# Sheet1.net
KiCad netlist of a schematic drawn in Altium Designer
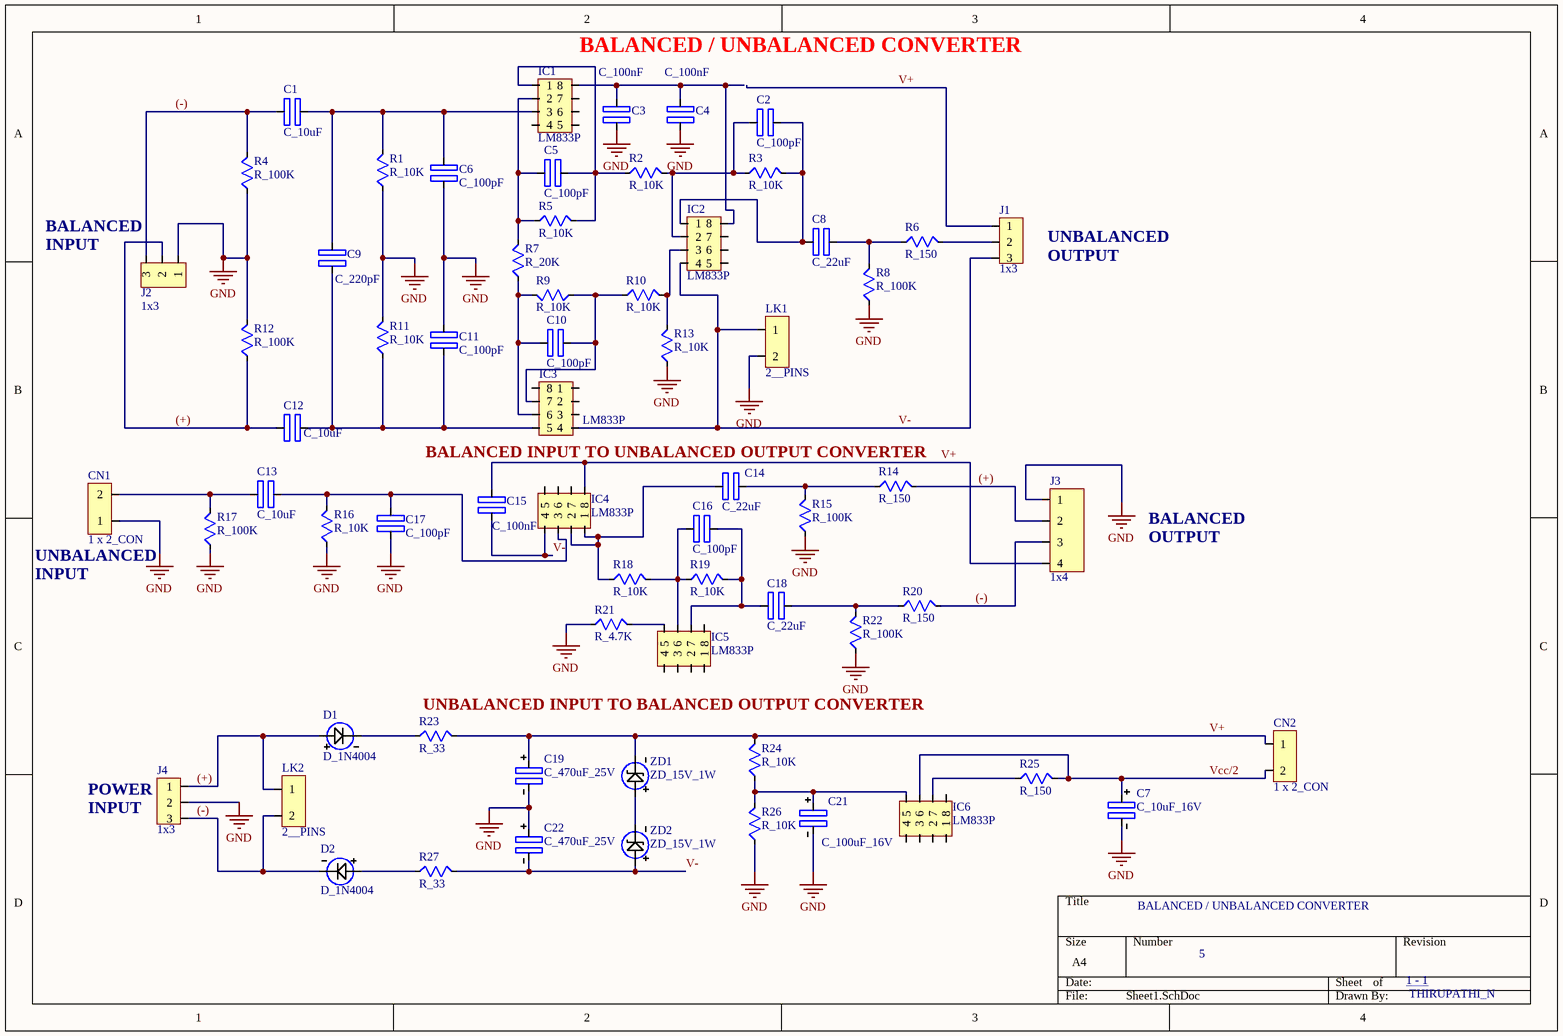
[diagram p0: Sheet1.SchDoc]

(export (version "E")
  (design (tool "Eeschema 10.0.6"))
  (components
    (comp (ref "C1")
      (value "C_10uF")
      (footprint "C_10uF")
      (description "CAP ALUM 10UF 20% 400V RADIAL")
      (fields
        (field (name "MANUFACTURER") "Nichicon")
        (field (name "MANUFACTURER PART NUMBER") "UCA2G100MPD1TD")
      )
      (libsource (lib "Schlib1") (part "C_10uF"))
    )
    (comp (ref "C2")
      (value "C_100pF")
      (footprint "C_100pF")
      (description "CAPACITOR CERAMIC 100PF 3000V C0G 5%, RAD")
      (fields
        (field (name "MANUFACTURER") "KEMET")
        (field (name "MANUFACTURER PART NUMBER") "C330C101JHG5TA")
      )
      (libsource (lib "Schlib1") (part "C_100pF"))
    )
    (comp (ref "C3")
      (value "C_100nF")
      (footprint "C_100nF")
      (description "NICHICON   UVR2A0R1MDD1TD   ALUMINUM ELECTROLYTIC CAPACITOR, 0.1UF, 100V, 20%, RADIAL")
      (fields
        (field (name "MANUFACTURER") "Nichicon")
        (field (name "MANUFACTURER PART NUMBER") "UVR2A0R1MDD1TD")
      )
      (libsource (lib "Schlib1") (part "C_100nF"))
    )
    (comp (ref "C4")
      (value "C_100nF")
      (footprint "C_100nF")
      (description "NICHICON   UVR2A0R1MDD1TD   ALUMINUM ELECTROLYTIC CAPACITOR, 0.1UF, 100V, 20%, RADIAL")
      (fields
        (field (name "MANUFACTURER") "Nichicon")
        (field (name "MANUFACTURER PART NUMBER") "UVR2A0R1MDD1TD")
      )
      (libsource (lib "Schlib1") (part "C_100nF"))
    )
    (comp (ref "C5")
      (value "C_100pF")
      (footprint "C_100pF")
      (description "CAPACITOR CERAMIC 100PF 3000V C0G 5%, RAD")
      (fields
        (field (name "MANUFACTURER") "KEMET")
        (field (name "MANUFACTURER PART NUMBER") "C330C101JHG5TA")
      )
      (libsource (lib "Schlib1") (part "C_100pF"))
    )
    (comp (ref "C6")
      (value "C_100pF")
      (footprint "C_100pF")
      (description "CAPACITOR CERAMIC 100PF 3000V C0G 5%, RAD")
      (fields
        (field (name "MANUFACTURER") "KEMET")
        (field (name "MANUFACTURER PART NUMBER") "C330C101JHG5TA")
      )
      (libsource (lib "Schlib1") (part "C_100pF"))
    )
    (comp (ref "C7")
      (value "C_10uF_16V")
      (footprint "C_10uF_16V")
      (description "CAPACITOR ALUM ELECT, 10UF, 16V, 20%, RADIAL")
      (fields
        (field (name "MANUFACTURER") "Nichicon")
        (field (name "MANUFACTURER PART NUMBER") "UST1C100MDD1TE")
      )
      (libsource (lib "Schlib1") (part "C_10uF_16V"))
    )
    (comp (ref "C8")
      (value "C_22uF")
      (footprint "C_22uF")
      (description "Cap Aluminum Lytic 22uF 50V 20% (5 X 11mm) Radial 2.5mm 95mA 2000h 85C Ammo Pack")
      (fields
        (field (name "MANUFACTURER") "Nichicon")
        (field (name "MANUFACTURER PART NUMBER") "UVR1H220MDD1TD")
      )
      (libsource (lib "Schlib1") (part "C_22uF"))
    )
    (comp (ref "C9")
      (value "C_220pF")
      (footprint "C_220pF")
      (fields
        (field (name "MANUFACTURER") "Vishay BCcomponents")
        (field (name "MANUFACTURER PART NUMBER") "F221K25Y5RN6UK5R")
        (field (name "TOLERANCE") "10%")
      )
      (libsource (lib "Schlib1") (part "C_220pF"))
    )
    (comp (ref "C10")
      (value "C_100pF")
      (footprint "C_100pF")
      (description "CAPACITOR CERAMIC 100PF 3000V C0G 5%, RAD")
      (fields
        (field (name "MANUFACTURER") "KEMET")
        (field (name "MANUFACTURER PART NUMBER") "C330C101JHG5TA")
      )
      (libsource (lib "Schlib1") (part "C_100pF"))
    )
    (comp (ref "C11")
      (value "C_100pF")
      (footprint "C_100pF")
      (description "CAPACITOR CERAMIC 100PF 3000V C0G 5%, RAD")
      (fields
        (field (name "MANUFACTURER") "KEMET")
        (field (name "MANUFACTURER PART NUMBER") "C330C101JHG5TA")
      )
      (libsource (lib "Schlib1") (part "C_100pF"))
    )
    (comp (ref "C12")
      (value "C_10uF")
      (footprint "C_10uF")
      (description "CAP ALUM 10UF 20% 400V RADIAL")
      (fields
        (field (name "MANUFACTURER") "Nichicon")
        (field (name "MANUFACTURER PART NUMBER") "UCA2G100MPD1TD")
      )
      (libsource (lib "Schlib1") (part "C_10uF"))
    )
    (comp (ref "C13")
      (value "C_10uF")
      (footprint "C_10uF")
      (description "CAP ALUM 10UF 20% 400V RADIAL")
      (fields
        (field (name "MANUFACTURER") "Nichicon")
        (field (name "MANUFACTURER PART NUMBER") "UCA2G100MPD1TD")
      )
      (libsource (lib "Schlib1") (part "C_10uF"))
    )
    (comp (ref "C14")
      (value "C_22uF")
      (footprint "C_22uF")
      (description "Cap Aluminum Lytic 22uF 50V 20% (5 X 11mm) Radial 2.5mm 95mA 2000h 85C Ammo Pack")
      (fields
        (field (name "MANUFACTURER") "Nichicon")
        (field (name "MANUFACTURER PART NUMBER") "UVR1H220MDD1TD")
      )
      (libsource (lib "Schlib1") (part "C_22uF"))
    )
    (comp (ref "C15")
      (value "C_100nF")
      (footprint "C_100nF")
      (description "NICHICON   UVR2A0R1MDD1TD   ALUMINUM ELECTROLYTIC CAPACITOR, 0.1UF, 100V, 20%, RADIAL")
      (fields
        (field (name "MANUFACTURER") "Nichicon")
        (field (name "MANUFACTURER PART NUMBER") "UVR2A0R1MDD1TD")
      )
      (libsource (lib "Schlib1") (part "C_100nF"))
    )
    (comp (ref "C16")
      (value "C_100pF")
      (footprint "C_100pF")
      (description "CAPACITOR CERAMIC 100PF 3000V C0G 5%, RAD")
      (fields
        (field (name "MANUFACTURER") "KEMET")
        (field (name "MANUFACTURER PART NUMBER") "C330C101JHG5TA")
      )
      (libsource (lib "Schlib1") (part "C_100pF"))
    )
    (comp (ref "C17")
      (value "C_100pF")
      (footprint "C_100pF")
      (description "CAPACITOR CERAMIC 100PF 3000V C0G 5%, RAD")
      (fields
        (field (name "MANUFACTURER") "KEMET")
        (field (name "MANUFACTURER PART NUMBER") "C330C101JHG5TA")
      )
      (libsource (lib "Schlib1") (part "C_100pF"))
    )
    (comp (ref "C18")
      (value "C_22uF")
      (footprint "C_22uF")
      (description "Cap Aluminum Lytic 22uF 50V 20% (5 X 11mm) Radial 2.5mm 95mA 2000h 85C Ammo Pack")
      (fields
        (field (name "MANUFACTURER") "Nichicon")
        (field (name "MANUFACTURER PART NUMBER") "UVR1H220MDD1TD")
      )
      (libsource (lib "Schlib1") (part "C_22uF"))
    )
    (comp (ref "C19")
      (value "C_470uF_25V")
      (footprint "C_25V_470uF")
      (fields
        (field (name "MANUFACTURER") "Nichicon")
        (field (name "MANUFACTURER PART NUMBER") "UHE1E471MPD6TD")
        (field (name "TOLERANCE") "20%")
      )
      (libsource (lib "Schlib1") (part "C_470uF_25V"))
    )
    (comp (ref "C21")
      (value "C_100uF_16V")
      (footprint "C_100uF_16V")
      (description "Cap Aluminum Lytic 100uF 16V 20% (6.3 X 7mm) Radial 2.5mm 110mA 1000h 105°C Ammo")
      (fields
        (field (name "MANUFACTURER") "KEMET")
        (field (name "MANUFACTURER PART NUMBER") "ESS107M016AE2EA")
      )
      (libsource (lib "Schlib1") (part "C_100uF_16V"))
    )
    (comp (ref "C22")
      (value "C_470uF_25V")
      (footprint "C_25V_470uF")
      (fields
        (field (name "MANUFACTURER") "Nichicon")
        (field (name "MANUFACTURER PART NUMBER") "UHE1E471MPD6TD")
        (field (name "TOLERANCE") "20%")
      )
      (libsource (lib "Schlib1") (part "C_470uF_25V"))
    )
    (comp (ref "CN1")
      (value "1 x 2_CON")
      (footprint "1*2_CONNECTOR")
      (description "TERM BLK 2POS SIDE ENTRY 5MM PCB")
      (fields
        (field (name "MANUFACTURER") "Wurth Electronics")
        (field (name "MANUFACTURER PART NUMBER") "691137710002")
      )
      (libsource (lib "") (part "1 x 2_CON_1"))
    )
    (comp (ref "CN2")
      (value "1 x 2_CON")
      (footprint "1*2_CONNECTOR")
      (description "TERM BLK 2POS SIDE ENTRY 5MM PCB")
      (fields
        (field (name "MANUFACTURER") "Wurth Electronics")
        (field (name "MANUFACTURER PART NUMBER") "691137710002")
      )
      (libsource (lib "Schlib1") (part "1 x 2_CON"))
    )
    (comp (ref "D1")
      (value "D_1N4004")
      (footprint "D_IN4004")
      (description "DIODES INC. - 1N4004-T - Standard Recovery Diode, 400 V, 1 A, Single, 1 V, 30 A")
      (fields (field (name "MANUFACTURER") "Diodes") (field (name "MANUFACTURER PART NUMBER") "1N4004-T"))
      (libsource (lib "Schlib1") (part "D_1N4004"))
    )
    (comp (ref "D2")
      (value "D_1N4004")
      (footprint "D_IN4004")
      (description "DIODES INC. - 1N4004-T - Standard Recovery Diode, 400 V, 1 A, Single, 1 V, 30 A")
      (fields (field (name "MANUFACTURER") "Diodes") (field (name "MANUFACTURER PART NUMBER") "1N4004-T"))
      (libsource (lib "Schlib1") (part "D_1N4004"))
    )
    (comp (ref "IC1")
      (value "LM833P")
      (footprint "IC_833")
      (description "OP Amp Dual GP 18V/36V 8-Pin PDIP Tube")
      (fields (field (name "MANUFACTURER") "Texas Instruments"))
      (libsource (lib "Schlib1") (part "LM833P"))
    )
    (comp (ref "IC2")
      (value "LM833P")
      (footprint "IC_833")
      (description "OP Amp Dual GP 18V/36V 8-Pin PDIP Tube")
      (fields (field (name "MANUFACTURER") "Texas Instruments"))
      (libsource (lib "Schlib1") (part "LM833P"))
    )
    (comp (ref "IC3")
      (value "LM833P")
      (footprint "IC_833")
      (description "OP Amp Dual GP 18V/36V 8-Pin PDIP Tube")
      (fields (field (name "MANUFACTURER") "Texas Instruments"))
      (libsource (lib "") (part "LM833P_1"))
    )
    (comp (ref "IC4")
      (value "LM833P")
      (footprint "IC_833")
      (description "OP Amp Dual GP 18V/36V 8-Pin PDIP Tube")
      (fields (field (name "MANUFACTURER") "Texas Instruments"))
      (libsource (lib "Schlib1") (part "LM833P"))
    )
    (comp (ref "IC5")
      (value "LM833P")
      (footprint "IC_833")
      (description "OP Amp Dual GP 18V/36V 8-Pin PDIP Tube")
      (fields (field (name "MANUFACTURER") "Texas Instruments"))
      (libsource (lib "Schlib1") (part "LM833P"))
    )
    (comp (ref "IC6")
      (value "LM833P")
      (footprint "IC_833")
      (description "OP Amp Dual GP 18V/36V 8-Pin PDIP Tube")
      (fields (field (name "MANUFACTURER") "Texas Instruments"))
      (libsource (lib "Schlib1") (part "LM833P"))
    )
    (comp (ref "J1")
      (value "1x3")
      (footprint "1*3_CONNECTOR")
      (description "Fixed Terminal Blocks WR-TBL SMT Model7097 3Pin 5mm Hztl")
      (fields
        (field (name "MANUFACTURER") "Wurth Electronics Midcom")
        (field (name "MANUFACTURER PART NUMBER") "691709710303")
      )
      (libsource (lib "") (part "1x3_1"))
    )
    (comp (ref "J2")
      (value "1x3")
      (footprint "1*3_CONNECTOR")
      (description "Fixed Terminal Blocks WR-TBL SMT Model7097 3Pin 5mm Hztl")
      (fields
        (field (name "MANUFACTURER") "Wurth Electronics Midcom")
        (field (name "MANUFACTURER PART NUMBER") "691709710303")
      )
      (libsource (lib "Schlib1") (part "1x3"))
    )
    (comp (ref "J3")
      (value "1x4")
      (footprint "1*4_CONNECTOR")
      (description "TERM BLK 4POS SIDE ENTRY 5MM PCB")
      (fields
        (field (name "MANUFACTURER") "Wurth Electronics")
        (field (name "MANUFACTURER PART NUMBER") "691137710004")
      )
      (libsource (lib "Schlib1") (part "1x4"))
    )
    (comp (ref "J4")
      (value "1x3")
      (footprint "1*3_CONNECTOR")
      (description "Fixed Terminal Blocks WR-TBL SMT Model7097 3Pin 5mm Hztl")
      (fields
        (field (name "MANUFACTURER") "Wurth Electronics Midcom")
        (field (name "MANUFACTURER PART NUMBER") "691709710303")
      )
      (libsource (lib "Schlib1") (part "1x3"))
    )
    (comp (ref "LK1")
      (value "2__PINS")
      (footprint "2_PIN")
      (description "HARWIN - M20-9990246 - CONNECTOR, HEADER, 2 POSITION, 1ROW, 2.54MM")
      (fields (field (name "MANUFACTURER") "Harwin") (field (name "MANUFACTURER PART NUMBER") "M20-9990246"))
      (libsource (lib "Schlib1") (part "2__PINS"))
    )
    (comp (ref "LK2")
      (value "2__PINS")
      (footprint "2_PIN")
      (description "HARWIN - M20-9990246 - CONNECTOR, HEADER, 2 POSITION, 1ROW, 2.54MM")
      (fields (field (name "MANUFACTURER") "Harwin") (field (name "MANUFACTURER PART NUMBER") "M20-9990246"))
      (libsource (lib "Schlib1") (part "2__PINS"))
    )
    (comp (ref "R1")
      (value "R_10K")
      (footprint "CF_RESISTOR_FP")
      (description "RES 10K OHM 1/4W 5% AXIAL")
      (fields
        (field (name "MANUFACTURER") "Stackpole Electronics")
        (field (name "MANUFACTURER PART NUMBER") "CF14JT10K0")
      )
      (libsource (lib "Schlib1") (part "R_10K"))
    )
    (comp (ref "R2")
      (value "R_10K")
      (footprint "CF_RESISTOR_FP")
      (description "RES 10K OHM 1/4W 5% AXIAL")
      (fields
        (field (name "MANUFACTURER") "Stackpole Electronics")
        (field (name "MANUFACTURER PART NUMBER") "CF14JT10K0")
      )
      (libsource (lib "Schlib1") (part "R_10K"))
    )
    (comp (ref "R3")
      (value "R_10K")
      (footprint "CF_RESISTOR_FP")
      (description "RES 10K OHM 1/4W 5% AXIAL")
      (fields
        (field (name "MANUFACTURER") "Stackpole Electronics")
        (field (name "MANUFACTURER PART NUMBER") "CF14JT10K0")
      )
      (libsource (lib "Schlib1") (part "R_10K"))
    )
    (comp (ref "R4")
      (value "R_100K")
      (footprint "CF_RESISTOR_FP")
      (description "RES 100K OHM 1/4W 5% AXIAL")
      (fields
        (field (name "MANUFACTURER") "Stackpole Electronics")
        (field (name "MANUFACTURER PART NUMBER") "CF14JT100K")
      )
      (libsource (lib "Schlib1") (part "R_100K"))
    )
    (comp (ref "R5")
      (value "R_10K")
      (footprint "CF_RESISTOR_FP")
      (description "RES 10K OHM 1/4W 5% AXIAL")
      (fields
        (field (name "MANUFACTURER") "Stackpole Electronics")
        (field (name "MANUFACTURER PART NUMBER") "CF14JT10K0")
      )
      (libsource (lib "Schlib1") (part "R_10K"))
    )
    (comp (ref "R6")
      (value "R_150")
      (footprint "CF_RESISTOR_FP")
      (description "Res Carbon Film 150 Ohm 5% 1/4W -400ppm/C to 0ppm/C Conformal AXL Thru-Hole T/R")
      (fields
        (field (name "MANUFACTURER") "Stackpole Electronics")
        (field (name "MANUFACTURER PART NUMBER") "CF14JT150R")
      )
      (libsource (lib "Schlib1") (part "R_150"))
    )
    (comp (ref "R7")
      (value "R_20K")
      (footprint "CF_RESISTOR_FP")
      (description "RES 20K OHM 1/2W 5% AXIAL")
      (fields
        (field (name "MANUFACTURER") "Stackpole Electronics")
        (field (name "MANUFACTURER PART NUMBER") "CF12JT20K0")
      )
      (libsource (lib "Schlib1") (part "R_20K"))
    )
    (comp (ref "R8")
      (value "R_100K")
      (footprint "CF_RESISTOR_FP")
      (description "RES 100K OHM 1/4W 5% AXIAL")
      (fields
        (field (name "MANUFACTURER") "Stackpole Electronics")
        (field (name "MANUFACTURER PART NUMBER") "CF14JT100K")
      )
      (libsource (lib "Schlib1") (part "R_100K"))
    )
    (comp (ref "R9")
      (value "R_10K")
      (footprint "CF_RESISTOR_FP")
      (description "RES 10K OHM 1/4W 5% AXIAL")
      (fields
        (field (name "MANUFACTURER") "Stackpole Electronics")
        (field (name "MANUFACTURER PART NUMBER") "CF14JT10K0")
      )
      (libsource (lib "Schlib1") (part "R_10K"))
    )
    (comp (ref "R10")
      (value "R_10K")
      (footprint "CF_RESISTOR_FP")
      (description "RES 10K OHM 1/4W 5% AXIAL")
      (fields
        (field (name "MANUFACTURER") "Stackpole Electronics")
        (field (name "MANUFACTURER PART NUMBER") "CF14JT10K0")
      )
      (libsource (lib "Schlib1") (part "R_10K"))
    )
    (comp (ref "R11")
      (value "R_10K")
      (footprint "CF_RESISTOR_FP")
      (description "RES 10K OHM 1/4W 5% AXIAL")
      (fields
        (field (name "MANUFACTURER") "Stackpole Electronics")
        (field (name "MANUFACTURER PART NUMBER") "CF14JT10K0")
      )
      (libsource (lib "Schlib1") (part "R_10K"))
    )
    (comp (ref "R12")
      (value "R_100K")
      (footprint "CF_RESISTOR_FP")
      (description "RES 100K OHM 1/4W 5% AXIAL")
      (fields
        (field (name "MANUFACTURER") "Stackpole Electronics")
        (field (name "MANUFACTURER PART NUMBER") "CF14JT100K")
      )
      (libsource (lib "Schlib1") (part "R_100K"))
    )
    (comp (ref "R13")
      (value "R_10K")
      (footprint "CF_RESISTOR_FP")
      (description "RES 10K OHM 1/4W 5% AXIAL")
      (fields
        (field (name "MANUFACTURER") "Stackpole Electronics")
        (field (name "MANUFACTURER PART NUMBER") "CF14JT10K0")
      )
      (libsource (lib "Schlib1") (part "R_10K"))
    )
    (comp (ref "R14")
      (value "R_150")
      (footprint "CF_RESISTOR_FP")
      (description "Res Carbon Film 150 Ohm 5% 1/4W -400ppm/C to 0ppm/C Conformal AXL Thru-Hole T/R")
      (fields
        (field (name "MANUFACTURER") "Stackpole Electronics")
        (field (name "MANUFACTURER PART NUMBER") "CF14JT150R")
      )
      (libsource (lib "Schlib1") (part "R_150"))
    )
    (comp (ref "R15")
      (value "R_100K")
      (footprint "CF_RESISTOR_FP")
      (description "RES 100K OHM 1/4W 5% AXIAL")
      (fields
        (field (name "MANUFACTURER") "Stackpole Electronics")
        (field (name "MANUFACTURER PART NUMBER") "CF14JT100K")
      )
      (libsource (lib "Schlib1") (part "R_100K"))
    )
    (comp (ref "R16")
      (value "R_10K")
      (footprint "CF_RESISTOR_FP")
      (description "RES 10K OHM 1/4W 5% AXIAL")
      (fields
        (field (name "MANUFACTURER") "Stackpole Electronics")
        (field (name "MANUFACTURER PART NUMBER") "CF14JT10K0")
      )
      (libsource (lib "Schlib1") (part "R_10K"))
    )
    (comp (ref "R17")
      (value "R_100K")
      (footprint "CF_RESISTOR_FP")
      (description "RES 100K OHM 1/4W 5% AXIAL")
      (fields
        (field (name "MANUFACTURER") "Stackpole Electronics")
        (field (name "MANUFACTURER PART NUMBER") "CF14JT100K")
      )
      (libsource (lib "Schlib1") (part "R_100K"))
    )
    (comp (ref "R18")
      (value "R_10K")
      (footprint "CF_RESISTOR_FP")
      (description "RES 10K OHM 1/4W 5% AXIAL")
      (fields
        (field (name "MANUFACTURER") "Stackpole Electronics")
        (field (name "MANUFACTURER PART NUMBER") "CF14JT10K0")
      )
      (libsource (lib "Schlib1") (part "R_10K"))
    )
    (comp (ref "R19")
      (value "R_10K")
      (footprint "CF_RESISTOR_FP")
      (description "RES 10K OHM 1/4W 5% AXIAL")
      (fields
        (field (name "MANUFACTURER") "Stackpole Electronics")
        (field (name "MANUFACTURER PART NUMBER") "CF14JT10K0")
      )
      (libsource (lib "Schlib1") (part "R_10K"))
    )
    (comp (ref "R20")
      (value "R_150")
      (footprint "CF_RESISTOR_FP")
      (description "Res Carbon Film 150 Ohm 5% 1/4W -400ppm/C to 0ppm/C Conformal AXL Thru-Hole T/R")
      (fields
        (field (name "MANUFACTURER") "Stackpole Electronics")
        (field (name "MANUFACTURER PART NUMBER") "CF14JT150R")
      )
      (libsource (lib "Schlib1") (part "R_150"))
    )
    (comp (ref "R21")
      (value "R_4.7K")
      (footprint "R_4.7K")
      (fields
        (field (name "MANUFACTURER") "Ohmite")
        (field (name "MANUFACTURER PART NUMBER") "OY472KE")
        (field (name "TOLERANCE") "10%")
      )
      (libsource (lib "Schlib1") (part "R_4.7K"))
    )
    (comp (ref "R22")
      (value "R_100K")
      (footprint "CF_RESISTOR_FP")
      (description "RES 100K OHM 1/4W 5% AXIAL")
      (fields
        (field (name "MANUFACTURER") "Stackpole Electronics")
        (field (name "MANUFACTURER PART NUMBER") "CF14JT100K")
      )
      (libsource (lib "Schlib1") (part "R_100K"))
    )
    (comp (ref "R23")
      (value "R_33")
      (footprint "CF_RESISTOR_FP")
      (description "RES 33 OHM 1/2W 5% AXIAL")
      (fields
        (field (name "MANUFACTURER") "Stackpole Electronics")
        (field (name "MANUFACTURER PART NUMBER") "CF12JT33R0")
      )
      (libsource (lib "Schlib1") (part "R_33"))
    )
    (comp (ref "R24")
      (value "R_10K")
      (footprint "CF_RESISTOR_FP")
      (description "RES 10K OHM 1/4W 5% AXIAL")
      (fields
        (field (name "MANUFACTURER") "Stackpole Electronics")
        (field (name "MANUFACTURER PART NUMBER") "CF14JT10K0")
      )
      (libsource (lib "Schlib1") (part "R_10K"))
    )
    (comp (ref "R25")
      (value "R_150")
      (footprint "CF_RESISTOR_FP")
      (description "Res Carbon Film 150 Ohm 5% 1/4W -400ppm/C to 0ppm/C Conformal AXL Thru-Hole T/R")
      (fields
        (field (name "MANUFACTURER") "Stackpole Electronics")
        (field (name "MANUFACTURER PART NUMBER") "CF14JT150R")
      )
      (libsource (lib "Schlib1") (part "R_150"))
    )
    (comp (ref "R26")
      (value "R_10K")
      (footprint "CF_RESISTOR_FP")
      (description "RES 10K OHM 1/4W 5% AXIAL")
      (fields
        (field (name "MANUFACTURER") "Stackpole Electronics")
        (field (name "MANUFACTURER PART NUMBER") "CF14JT10K0")
      )
      (libsource (lib "Schlib1") (part "R_10K"))
    )
    (comp (ref "R27")
      (value "R_33")
      (footprint "CF_RESISTOR_FP")
      (description "RES 33 OHM 1/2W 5% AXIAL")
      (fields
        (field (name "MANUFACTURER") "Stackpole Electronics")
        (field (name "MANUFACTURER PART NUMBER") "CF12JT33R0")
      )
      (libsource (lib "Schlib1") (part "R_33"))
    )
    (comp (ref "ZD1")
      (value "ZD_15V_1W")
      (footprint "ZR_15V_1W")
      (description "GLOVE, POLYAMIDE, L/FREE, PU, SIZE 6 - More Details")
      (fields
        (field (name "MANUFACTURER") "NXP Semiconductors")
        (field (name "MANUFACTURER PART NUMBER") "BZV85-C15,113")
      )
      (libsource (lib "Schlib1") (part "ZD_15V_1W"))
    )
    (comp (ref "ZD2")
      (value "ZD_15V_1W")
      (footprint "ZR_15V_1W")
      (description "GLOVE, POLYAMIDE, L/FREE, PU, SIZE 6 - More Details")
      (fields
        (field (name "MANUFACTURER") "NXP Semiconductors")
        (field (name "MANUFACTURER PART NUMBER") "BZV85-C15,113")
      )
      (libsource (lib "Schlib1") (part "ZD_15V_1W"))
    )
  )
  (nets
    (net (code "1") (name "/(+)") (class "Default")
      (node (ref "C12") (pin "0") (pinfunction "0_0") (pintype "passive"))
      (node (ref "D1") (pin "2") (pinfunction "2_2") (pintype "passive"))
      (node (ref "J2") (pin "2") (pinfunction "2_2") (pintype "passive"))
      (node (ref "J3") (pin "2") (pinfunction "2_2") (pintype "passive"))
      (node (ref "J4") (pin "1") (pinfunction "1_1") (pintype "passive"))
      (node (ref "LK2") (pin "1") (pinfunction "1_1") (pintype "passive"))
      (node (ref "R12") (pin "0") (pinfunction "0_0") (pintype "passive"))
      (node (ref "R14") (pin "1") (pinfunction "1_1") (pintype "passive"))
    )
    (net (code "2") (name "/(-)") (class "Default")
      (node (ref "C1") (pin "0") (pinfunction "0_0") (pintype "passive"))
      (node (ref "D2") (pin "1") (pinfunction "1_1") (pintype "passive"))
      (node (ref "J2") (pin "3") (pinfunction "3_3") (pintype "passive"))
      (node (ref "J3") (pin "3") (pinfunction "3_3") (pintype "passive"))
      (node (ref "J4") (pin "3") (pinfunction "3_3") (pintype "passive"))
      (node (ref "LK2") (pin "2") (pinfunction "2_2") (pintype "passive"))
      (node (ref "R20") (pin "1") (pinfunction "1_1") (pintype "passive"))
      (node (ref "R4") (pin "1") (pinfunction "1_1") (pintype "passive"))
    )
    (net (code "3") (name "/V+") (class "Default")
      (node (ref "C15") (pin "1") (pinfunction "1_1") (pintype "passive"))
      (node (ref "C19") (pin "0") (pinfunction "0_0") (pintype "passive"))
      (node (ref "CN2") (pin "1") (pinfunction "1_1") (pintype "passive"))
      (node (ref "IC4") (pin "8") (pinfunction "8_8") (pintype "passive"))
      (node (ref "J1") (pin "1") (pinfunction "1_1") (pintype "passive"))
      (node (ref "J3") (pin "4") (pinfunction "4_4") (pintype "passive"))
      (node (ref "R23") (pin "1") (pinfunction "1_1") (pintype "passive"))
      (node (ref "R24") (pin "1") (pinfunction "1_1") (pintype "passive"))
      (node (ref "ZD1") (pin "1") (pinfunction "1_1") (pintype "passive"))
    )
    (net (code "4") (name "/V-") (class "Default")
      (node (ref "C15") (pin "0") (pinfunction "0_0") (pintype "passive"))
      (node (ref "C22") (pin "1") (pinfunction "1_1") (pintype "passive"))
      (node (ref "IC2") (pin "4") (pinfunction "4_4") (pintype "passive"))
      (node (ref "IC3") (pin "4") (pinfunction "4_4") (pintype "passive"))
      (node (ref "IC4") (pin "4") (pinfunction "4_4") (pintype "passive"))
      (node (ref "J1") (pin "3") (pinfunction "3_3") (pintype "passive"))
      (node (ref "LK1") (pin "1") (pinfunction "1_1") (pintype "passive"))
      (node (ref "R27") (pin "1") (pinfunction "1_1") (pintype "passive"))
      (node (ref "ZD2") (pin "2") (pinfunction "2_2") (pintype "passive"))
    )
    (net (code "5") (name "/Vcc{slash}2") (class "Default")
      (node (ref "C7") (pin "0") (pinfunction "0_0") (pintype "passive"))
      (node (ref "CN2") (pin "2") (pinfunction "2_2") (pintype "passive"))
      (node (ref "IC6") (pin "6") (pinfunction "6_6") (pintype "passive"))
      (node (ref "R25") (pin "1") (pinfunction "1_1") (pintype "passive"))
    )
    (net (code "6") (name "GND") (class "Default")
      (node (ref "C11") (pin "1") (pinfunction "1_1") (pintype "passive"))
      (node (ref "C17") (pin "0") (pinfunction "0_0") (pintype "passive"))
      (node (ref "C19") (pin "1") (pinfunction "1_1") (pintype "passive"))
      (node (ref "C21") (pin "1") (pinfunction "1_1") (pintype "passive"))
      (node (ref "C22") (pin "0") (pinfunction "0_0") (pintype "passive"))
      (node (ref "C3") (pin "0") (pinfunction "0_0") (pintype "passive"))
      (node (ref "C4") (pin "0") (pinfunction "0_0") (pintype "passive"))
      (node (ref "C6") (pin "0") (pinfunction "0_0") (pintype "passive"))
      (node (ref "C7") (pin "1") (pinfunction "1_1") (pintype "passive"))
      (node (ref "CN1") (pin "1") (pinfunction "1_1") (pintype "passive"))
      (node (ref "J2") (pin "1") (pinfunction "1_1") (pintype "passive"))
      (node (ref "J3") (pin "1") (pinfunction "1_1") (pintype "passive"))
      (node (ref "J4") (pin "2") (pinfunction "2_2") (pintype "passive"))
      (node (ref "LK1") (pin "2") (pinfunction "2_2") (pintype "passive"))
      (node (ref "R1") (pin "0") (pinfunction "0_0") (pintype "passive"))
      (node (ref "R11") (pin "1") (pinfunction "1_1") (pintype "passive"))
      (node (ref "R12") (pin "1") (pinfunction "1_1") (pintype "passive"))
      (node (ref "R13") (pin "0") (pinfunction "0_0") (pintype "passive"))
      (node (ref "R15") (pin "0") (pinfunction "0_0") (pintype "passive"))
      (node (ref "R16") (pin "0") (pinfunction "0_0") (pintype "passive"))
      (node (ref "R17") (pin "0") (pinfunction "0_0") (pintype "passive"))
      (node (ref "R21") (pin "0") (pinfunction "0_0") (pintype "passive"))
      (node (ref "R22") (pin "0") (pinfunction "0_0") (pintype "passive"))
      (node (ref "R26") (pin "0") (pinfunction "0_0") (pintype "passive"))
      (node (ref "R4") (pin "0") (pinfunction "0_0") (pintype "passive"))
      (node (ref "R8") (pin "0") (pinfunction "0_0") (pintype "passive"))
    )
    (net (code "7") (name "Net-(C1-Pad1)") (class "Default")
      (node (ref "C1") (pin "1") (pinfunction "1_1") (pintype "passive"))
      (node (ref "C6") (pin "1") (pinfunction "1_1") (pintype "passive"))
      (node (ref "C9") (pin "1") (pinfunction "1_1") (pintype "passive"))
      (node (ref "IC1") (pin "3") (pinfunction "3_3") (pintype "passive"))
      (node (ref "R1") (pin "1") (pinfunction "1_1") (pintype "passive"))
    )
    (net (code "8") (name "Net-(C2-Pad0)") (class "Default")
      (node (ref "C2") (pin "0") (pinfunction "0_0") (pintype "passive"))
      (node (ref "IC2") (pin "2") (pinfunction "2_2") (pintype "passive"))
      (node (ref "R2") (pin "1") (pinfunction "1_1") (pintype "passive"))
      (node (ref "R3") (pin "0") (pinfunction "0_0") (pintype "passive"))
    )
    (net (code "9") (name "Net-(C2-Pad1)") (class "Default")
      (node (ref "C2") (pin "1") (pinfunction "1_1") (pintype "passive"))
      (node (ref "C8") (pin "0") (pinfunction "0_0") (pintype "passive"))
      (node (ref "IC2") (pin "1") (pinfunction "1_1") (pintype "passive"))
      (node (ref "R3") (pin "1") (pinfunction "1_1") (pintype "passive"))
    )
    (net (code "10") (name "Net-(C3-Pad1)") (class "Default")
      (node (ref "C3") (pin "1") (pinfunction "1_1") (pintype "passive"))
      (node (ref "C4") (pin "1") (pinfunction "1_1") (pintype "passive"))
      (node (ref "IC1") (pin "8") (pinfunction "8_8") (pintype "passive"))
      (node (ref "IC2") (pin "8") (pinfunction "8_8") (pintype "passive"))
    )
    (net (code "11") (name "Net-(C5-Pad0)") (class "Default")
      (node (ref "C5") (pin "0") (pinfunction "0_0") (pintype "passive"))
      (node (ref "IC1") (pin "2") (pinfunction "2_2") (pintype "passive"))
      (node (ref "R5") (pin "0") (pinfunction "0_0") (pintype "passive"))
      (node (ref "R7") (pin "1") (pinfunction "1_1") (pintype "passive"))
    )
    (net (code "12") (name "Net-(C5-Pad1)") (class "Default")
      (node (ref "C5") (pin "1") (pinfunction "1_1") (pintype "passive"))
      (node (ref "IC1") (pin "1") (pinfunction "1_1") (pintype "passive"))
      (node (ref "R2") (pin "0") (pinfunction "0_0") (pintype "passive"))
      (node (ref "R5") (pin "1") (pinfunction "1_1") (pintype "passive"))
    )
    (net (code "13") (name "Net-(C8-Pad1)") (class "Default")
      (node (ref "C8") (pin "1") (pinfunction "1_1") (pintype "passive"))
      (node (ref "R6") (pin "0") (pinfunction "0_0") (pintype "passive"))
      (node (ref "R8") (pin "1") (pinfunction "1_1") (pintype "passive"))
    )
    (net (code "14") (name "Net-(C10-Pad0)") (class "Default")
      (node (ref "C10") (pin "0") (pinfunction "0_0") (pintype "passive"))
      (node (ref "IC3") (pin "7") (pinfunction "7_7") (pintype "passive"))
      (node (ref "R10") (pin "0") (pinfunction "0_0") (pintype "passive"))
      (node (ref "R9") (pin "0") (pinfunction "0_0") (pintype "passive"))
    )
    (net (code "15") (name "Net-(C10-Pad1)") (class "Default")
      (node (ref "C10") (pin "1") (pinfunction "1_1") (pintype "passive"))
      (node (ref "IC3") (pin "6") (pinfunction "6_6") (pintype "passive"))
      (node (ref "R7") (pin "0") (pinfunction "0_0") (pintype "passive"))
      (node (ref "R9") (pin "1") (pinfunction "1_1") (pintype "passive"))
    )
    (net (code "16") (name "Net-(C11-Pad0)") (class "Default")
      (node (ref "C11") (pin "0") (pinfunction "0_0") (pintype "passive"))
      (node (ref "C12") (pin "1") (pinfunction "1_1") (pintype "passive"))
      (node (ref "C9") (pin "0") (pinfunction "0_0") (pintype "passive"))
      (node (ref "IC3") (pin "5") (pinfunction "5_5") (pintype "passive"))
      (node (ref "R11") (pin "0") (pinfunction "0_0") (pintype "passive"))
    )
    (net (code "17") (name "Net-(C13-Pad0)") (class "Default")
      (node (ref "C13") (pin "0") (pinfunction "0_0") (pintype "passive"))
      (node (ref "CN1") (pin "2") (pinfunction "2_2") (pintype "passive"))
      (node (ref "R17") (pin "1") (pinfunction "1_1") (pintype "passive"))
    )
    (net (code "18") (name "Net-(C13-Pad1)") (class "Default")
      (node (ref "C13") (pin "1") (pinfunction "1_1") (pintype "passive"))
      (node (ref "C17") (pin "1") (pinfunction "1_1") (pintype "passive"))
      (node (ref "IC4") (pin "3") (pinfunction "3_3") (pintype "passive"))
      (node (ref "R16") (pin "1") (pinfunction "1_1") (pintype "passive"))
    )
    (net (code "19") (name "Net-(C14-Pad0)") (class "Default")
      (node (ref "C14") (pin "0") (pinfunction "0_0") (pintype "passive"))
      (node (ref "IC4") (pin "1") (pinfunction "1_1") (pintype "passive"))
      (node (ref "IC4") (pin "2") (pinfunction "2_2") (pintype "passive"))
      (node (ref "R18") (pin "0") (pinfunction "0_0") (pintype "passive"))
    )
    (net (code "20") (name "Net-(C14-Pad1)") (class "Default")
      (node (ref "C14") (pin "1") (pinfunction "1_1") (pintype "passive"))
      (node (ref "R14") (pin "0") (pinfunction "0_0") (pintype "passive"))
      (node (ref "R15") (pin "1") (pinfunction "1_1") (pintype "passive"))
    )
    (net (code "21") (name "Net-(C16-Pad0)") (class "Default")
      (node (ref "C16") (pin "0") (pinfunction "0_0") (pintype "passive"))
      (node (ref "IC5") (pin "6") (pinfunction "6_6") (pintype "passive"))
      (node (ref "R18") (pin "1") (pinfunction "1_1") (pintype "passive"))
      (node (ref "R19") (pin "0") (pinfunction "0_0") (pintype "passive"))
    )
    (net (code "22") (name "Net-(C16-Pad1)") (class "Default")
      (node (ref "C16") (pin "1") (pinfunction "1_1") (pintype "passive"))
      (node (ref "C18") (pin "0") (pinfunction "0_0") (pintype "passive"))
      (node (ref "IC5") (pin "7") (pinfunction "7_7") (pintype "passive"))
      (node (ref "R19") (pin "1") (pinfunction "1_1") (pintype "passive"))
    )
    (net (code "23") (name "Net-(C18-Pad1)") (class "Default")
      (node (ref "C18") (pin "1") (pinfunction "1_1") (pintype "passive"))
      (node (ref "R20") (pin "0") (pinfunction "0_0") (pintype "passive"))
      (node (ref "R22") (pin "1") (pinfunction "1_1") (pintype "passive"))
    )
    (net (code "24") (name "Net-(C21-Pad0)") (class "Default")
      (node (ref "C21") (pin "0") (pinfunction "0_0") (pintype "passive"))
      (node (ref "IC6") (pin "5") (pinfunction "5_5") (pintype "passive"))
      (node (ref "R24") (pin "0") (pinfunction "0_0") (pintype "passive"))
      (node (ref "R26") (pin "1") (pinfunction "1_1") (pintype "passive"))
    )
    (net (code "25") (name "Net-(D1-Pad1)") (class "Default")
      (node (ref "D1") (pin "1") (pinfunction "1_1") (pintype "passive"))
      (node (ref "R23") (pin "0") (pinfunction "0_0") (pintype "passive"))
    )
    (net (code "26") (name "Net-(D2-Pad2)") (class "Default")
      (node (ref "D2") (pin "2") (pinfunction "2_2") (pintype "passive"))
      (node (ref "R27") (pin "0") (pinfunction "0_0") (pintype "passive"))
    )
    (net (code "27") (name "Net-(IC2-Pad3)") (class "Default")
      (node (ref "IC2") (pin "3") (pinfunction "3_3") (pintype "passive"))
      (node (ref "R10") (pin "1") (pinfunction "1_1") (pintype "passive"))
      (node (ref "R13") (pin "1") (pinfunction "1_1") (pintype "passive"))
    )
    (net (code "28") (name "Net-(IC5-Pad5)") (class "Default")
      (node (ref "IC5") (pin "5") (pinfunction "5_5") (pintype "passive"))
      (node (ref "R21") (pin "1") (pinfunction "1_1") (pintype "passive"))
    )
    (net (code "29") (name "Net-(IC6-Pad7)") (class "Default")
      (node (ref "IC6") (pin "7") (pinfunction "7_7") (pintype "passive"))
      (node (ref "R25") (pin "0") (pinfunction "0_0") (pintype "passive"))
    )
    (net (code "30") (name "Net-(J1-Pad2)") (class "Default")
      (node (ref "J1") (pin "2") (pinfunction "2_2") (pintype "passive"))
      (node (ref "R6") (pin "1") (pinfunction "1_1") (pintype "passive"))
    )
    (net (code "31") (name "Net-(ZD1-Pad2)") (class "Default")
      (node (ref "ZD1") (pin "2") (pinfunction "2_2") (pintype "passive"))
      (node (ref "ZD2") (pin "1") (pinfunction "1_1") (pintype "passive"))
    )
    (net (code "32") (name "unconnected-(IC1-Pad4)") (class "Default")
      (node (ref "IC1") (pin "4") (pinfunction "4_4") (pintype "passive"))
    )
    (net (code "33") (name "unconnected-(IC1-Pad5)") (class "Default")
      (node (ref "IC1") (pin "5") (pinfunction "5_5") (pintype "passive"))
    )
    (net (code "34") (name "unconnected-(IC1-Pad6)") (class "Default")
      (node (ref "IC1") (pin "6") (pinfunction "6_6") (pintype "passive"))
    )
    (net (code "35") (name "unconnected-(IC1-Pad7)") (class "Default")
      (node (ref "IC1") (pin "7") (pinfunction "7_7") (pintype "passive"))
    )
    (net (code "36") (name "unconnected-(IC2-Pad5)") (class "Default")
      (node (ref "IC2") (pin "5") (pinfunction "5_5") (pintype "passive"))
    )
    (net (code "37") (name "unconnected-(IC2-Pad6)") (class "Default")
      (node (ref "IC2") (pin "6") (pinfunction "6_6") (pintype "passive"))
    )
    (net (code "38") (name "unconnected-(IC2-Pad7)") (class "Default")
      (node (ref "IC2") (pin "7") (pinfunction "7_7") (pintype "passive"))
    )
    (net (code "39") (name "unconnected-(IC3-Pad1)") (class "Default")
      (node (ref "IC3") (pin "1") (pinfunction "1_1") (pintype "passive"))
    )
    (net (code "40") (name "unconnected-(IC3-Pad2)") (class "Default")
      (node (ref "IC3") (pin "2") (pinfunction "2_2") (pintype "passive"))
    )
    (net (code "41") (name "unconnected-(IC3-Pad3)") (class "Default")
      (node (ref "IC3") (pin "3") (pinfunction "3_3") (pintype "passive"))
    )
    (net (code "42") (name "unconnected-(IC3-Pad8)") (class "Default")
      (node (ref "IC3") (pin "8") (pinfunction "8_8") (pintype "passive"))
    )
    (net (code "43") (name "unconnected-(IC4-Pad5)") (class "Default")
      (node (ref "IC4") (pin "5") (pinfunction "5_5") (pintype "passive"))
    )
    (net (code "44") (name "unconnected-(IC4-Pad6)") (class "Default")
      (node (ref "IC4") (pin "6") (pinfunction "6_6") (pintype "passive"))
    )
    (net (code "45") (name "unconnected-(IC4-Pad7)") (class "Default")
      (node (ref "IC4") (pin "7") (pinfunction "7_7") (pintype "passive"))
    )
    (net (code "46") (name "unconnected-(IC5-Pad1)") (class "Default")
      (node (ref "IC5") (pin "1") (pinfunction "1_1") (pintype "passive"))
    )
    (net (code "47") (name "unconnected-(IC5-Pad2)") (class "Default")
      (node (ref "IC5") (pin "2") (pinfunction "2_2") (pintype "passive"))
    )
    (net (code "48") (name "unconnected-(IC5-Pad3)") (class "Default")
      (node (ref "IC5") (pin "3") (pinfunction "3_3") (pintype "passive"))
    )
    (net (code "49") (name "unconnected-(IC5-Pad4)") (class "Default")
      (node (ref "IC5") (pin "4") (pinfunction "4_4") (pintype "passive"))
    )
    (net (code "50") (name "unconnected-(IC5-Pad8)") (class "Default")
      (node (ref "IC5") (pin "8") (pinfunction "8_8") (pintype "passive"))
    )
    (net (code "51") (name "unconnected-(IC6-Pad1)") (class "Default")
      (node (ref "IC6") (pin "1") (pinfunction "1_1") (pintype "passive"))
    )
    (net (code "52") (name "unconnected-(IC6-Pad2)") (class "Default")
      (node (ref "IC6") (pin "2") (pinfunction "2_2") (pintype "passive"))
    )
    (net (code "53") (name "unconnected-(IC6-Pad3)") (class "Default")
      (node (ref "IC6") (pin "3") (pinfunction "3_3") (pintype "passive"))
    )
    (net (code "54") (name "unconnected-(IC6-Pad4)") (class "Default")
      (node (ref "IC6") (pin "4") (pinfunction "4_4") (pintype "passive"))
    )
    (net (code "55") (name "unconnected-(IC6-Pad8)") (class "Default")
      (node (ref "IC6") (pin "8") (pinfunction "8_8") (pintype "passive"))
    )
  )
)
